# can_transciever.net
KiCad netlist of a schematic drawn in Altium Designer
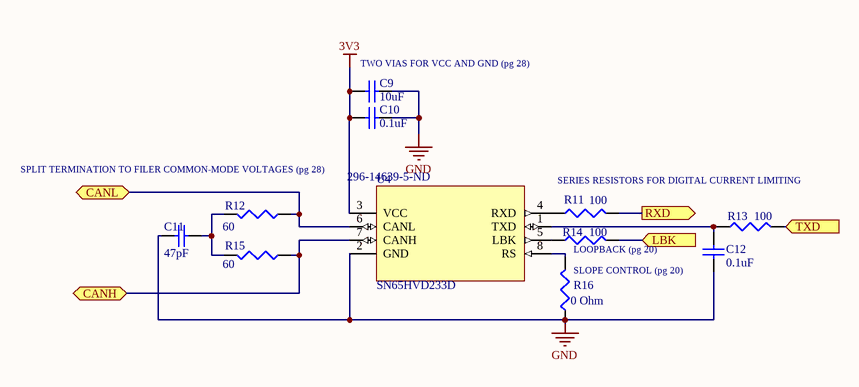
[diagram p0: can_transciever.SchDoc]

(export (version "E")
  (design (tool "Eeschema 10.0.6"))
  (components
    (comp (ref "C9")
      (value "10uF")
      (footprint "1608[0603]")
      (description "Capacitor (Semiconductor SIM Model)")
      (fields (field (name "PUBLISHER") "Altium Limited"))
      (libsource (lib "Miscellaneous Devices") (part "Cap Semi"))
    )
    (comp (ref "C10")
      (value "0.1uF")
      (footprint "1608[0603]")
      (description "Capacitor (Semiconductor SIM Model)")
      (fields (field (name "PUBLISHER") "Altium Limited"))
      (libsource (lib "Miscellaneous Devices") (part "Cap Semi"))
    )
    (comp (ref "C11")
      (value "47pF")
      (footprint "1608[0603]")
      (description "Capacitor (Semiconductor SIM Model)")
      (fields (field (name "PUBLISHER") "Altium Limited"))
      (libsource (lib "Miscellaneous Devices") (part "Cap Semi"))
    )
    (comp (ref "C12")
      (value "0.1uF")
      (footprint "1608[0603]")
      (description "Capacitor (Semiconductor SIM Model)")
      (fields (field (name "PUBLISHER") "Altium Limited"))
      (libsource (lib "Miscellaneous Devices") (part "Cap Semi"))
    )
    (comp (ref "R11")
      (value "100")
      (footprint "J1-0603")
      (description "Resistor")
      (fields (field (name "PUBLISHER") "Altium Limited"))
      (libsource (lib "Miscellaneous Devices") (part "Res3"))
    )
    (comp (ref "R12")
      (value "60")
      (footprint "J1-0603")
      (description "Resistor")
      (fields (field (name "PUBLISHER") "Altium Limited"))
      (libsource (lib "Miscellaneous Devices") (part "Res3"))
    )
    (comp (ref "R13")
      (value "100")
      (footprint "J1-0603")
      (description "Resistor")
      (fields (field (name "PUBLISHER") "Altium Limited"))
      (libsource (lib "Miscellaneous Devices") (part "Res3"))
    )
    (comp (ref "R14")
      (value "100")
      (footprint "J1-0603")
      (description "Resistor")
      (fields (field (name "PUBLISHER") "Altium Limited"))
      (libsource (lib "Miscellaneous Devices") (part "Res3"))
    )
    (comp (ref "R15")
      (value "60")
      (footprint "J1-0603")
      (description "Resistor")
      (fields (field (name "PUBLISHER") "Altium Limited"))
      (libsource (lib "Miscellaneous Devices") (part "Res3"))
    )
    (comp (ref "R16")
      (value "0 Ohm")
      (footprint "J1-0603")
      (description "Resistor")
      (fields (field (name "PUBLISHER") "Altium Limited"))
      (libsource (lib "Miscellaneous Devices") (part "Res3"))
    )
    (comp (ref "U4")
      (value "SN65HVD233D")
      (footprint "SOIC127P500X600-8N")
      (description "3.3V CAN Transceiver with Standby Mode, Loop-back 8-SOIC -40 to 125")
      (fields
        (field (name "MF") "Texas Instruments")
        (field (name "SUPPLIER PART NUMBER 1") "296-14639-5-ND")
      )
      (libsource (lib "ICs") (part "SN65HVD233D"))
    )
  )
  (nets
    (net (code "1") (name "/CANH") (class "Default")
      (node (ref "R15") (pin "1") (pinfunction "1_1") (pintype "passive"))
      (node (ref "U4") (pin "7") (pinfunction "CANH_7") (pintype "bidirectional"))
    )
    (net (code "2") (name "/CANL") (class "Default")
      (node (ref "R12") (pin "1") (pinfunction "1_1") (pintype "passive"))
      (node (ref "U4") (pin "6") (pinfunction "CANL_6") (pintype "bidirectional"))
    )
    (net (code "3") (name "/LBK") (class "Default")
      (node (ref "R14") (pin "2") (pinfunction "2_2") (pintype "passive"))
    )
    (net (code "4") (name "/RXD") (class "Default")
      (node (ref "R11") (pin "2") (pinfunction "2_2") (pintype "passive"))
    )
    (net (code "5") (name "/TXD") (class "Default")
      (node (ref "R13") (pin "2") (pinfunction "2_2") (pintype "passive"))
    )
    (net (code "6") (name "3V3") (class "Default")
      (node (ref "C10") (pin "2") (pinfunction "2_2") (pintype "passive"))
      (node (ref "C9") (pin "2") (pinfunction "2_2") (pintype "passive"))
      (node (ref "U4") (pin "3") (pinfunction "VCC_3") (pintype "power_in"))
    )
    (net (code "7") (name "GND") (class "Default")
      (node (ref "C10") (pin "1") (pinfunction "1_1") (pintype "passive"))
      (node (ref "C11") (pin "1") (pinfunction "1_1") (pintype "passive"))
      (node (ref "C12") (pin "1") (pinfunction "1_1") (pintype "passive"))
      (node (ref "C9") (pin "1") (pinfunction "1_1") (pintype "passive"))
      (node (ref "R16") (pin "1") (pinfunction "1_1") (pintype "passive"))
      (node (ref "U4") (pin "2") (pinfunction "GND_2") (pintype "power_in"))
    )
    (net (code "8") (name "Net-(C11-Pad2)") (class "Default")
      (node (ref "C11") (pin "2") (pinfunction "2_2") (pintype "passive"))
      (node (ref "R12") (pin "2") (pinfunction "2_2") (pintype "passive"))
      (node (ref "R15") (pin "2") (pinfunction "2_2") (pintype "passive"))
    )
    (net (code "9") (name "Net-(U4-LBK)") (class "Default")
      (node (ref "R14") (pin "1") (pinfunction "1_1") (pintype "passive"))
      (node (ref "U4") (pin "5") (pinfunction "LBK_5") (pintype "output"))
    )
    (net (code "10") (name "Net-(U4-RS)") (class "Default")
      (node (ref "R16") (pin "2") (pinfunction "2_2") (pintype "passive"))
      (node (ref "U4") (pin "8") (pinfunction "RS_8") (pintype "input"))
    )
    (net (code "11") (name "Net-(U4-RXD)") (class "Default")
      (node (ref "R11") (pin "1") (pinfunction "1_1") (pintype "passive"))
      (node (ref "U4") (pin "4") (pinfunction "RXD_4") (pintype "output"))
    )
    (net (code "12") (name "Net-(U4-TXD)") (class "Default")
      (node (ref "C12") (pin "2") (pinfunction "2_2") (pintype "passive"))
      (node (ref "R13") (pin "1") (pinfunction "1_1") (pintype "passive"))
      (node (ref "U4") (pin "1") (pinfunction "TXD_1") (pintype "bidirectional"))
    )
  )
)
